# 00A-095.net
KiCad netlist of a schematic drawn in EAGLE
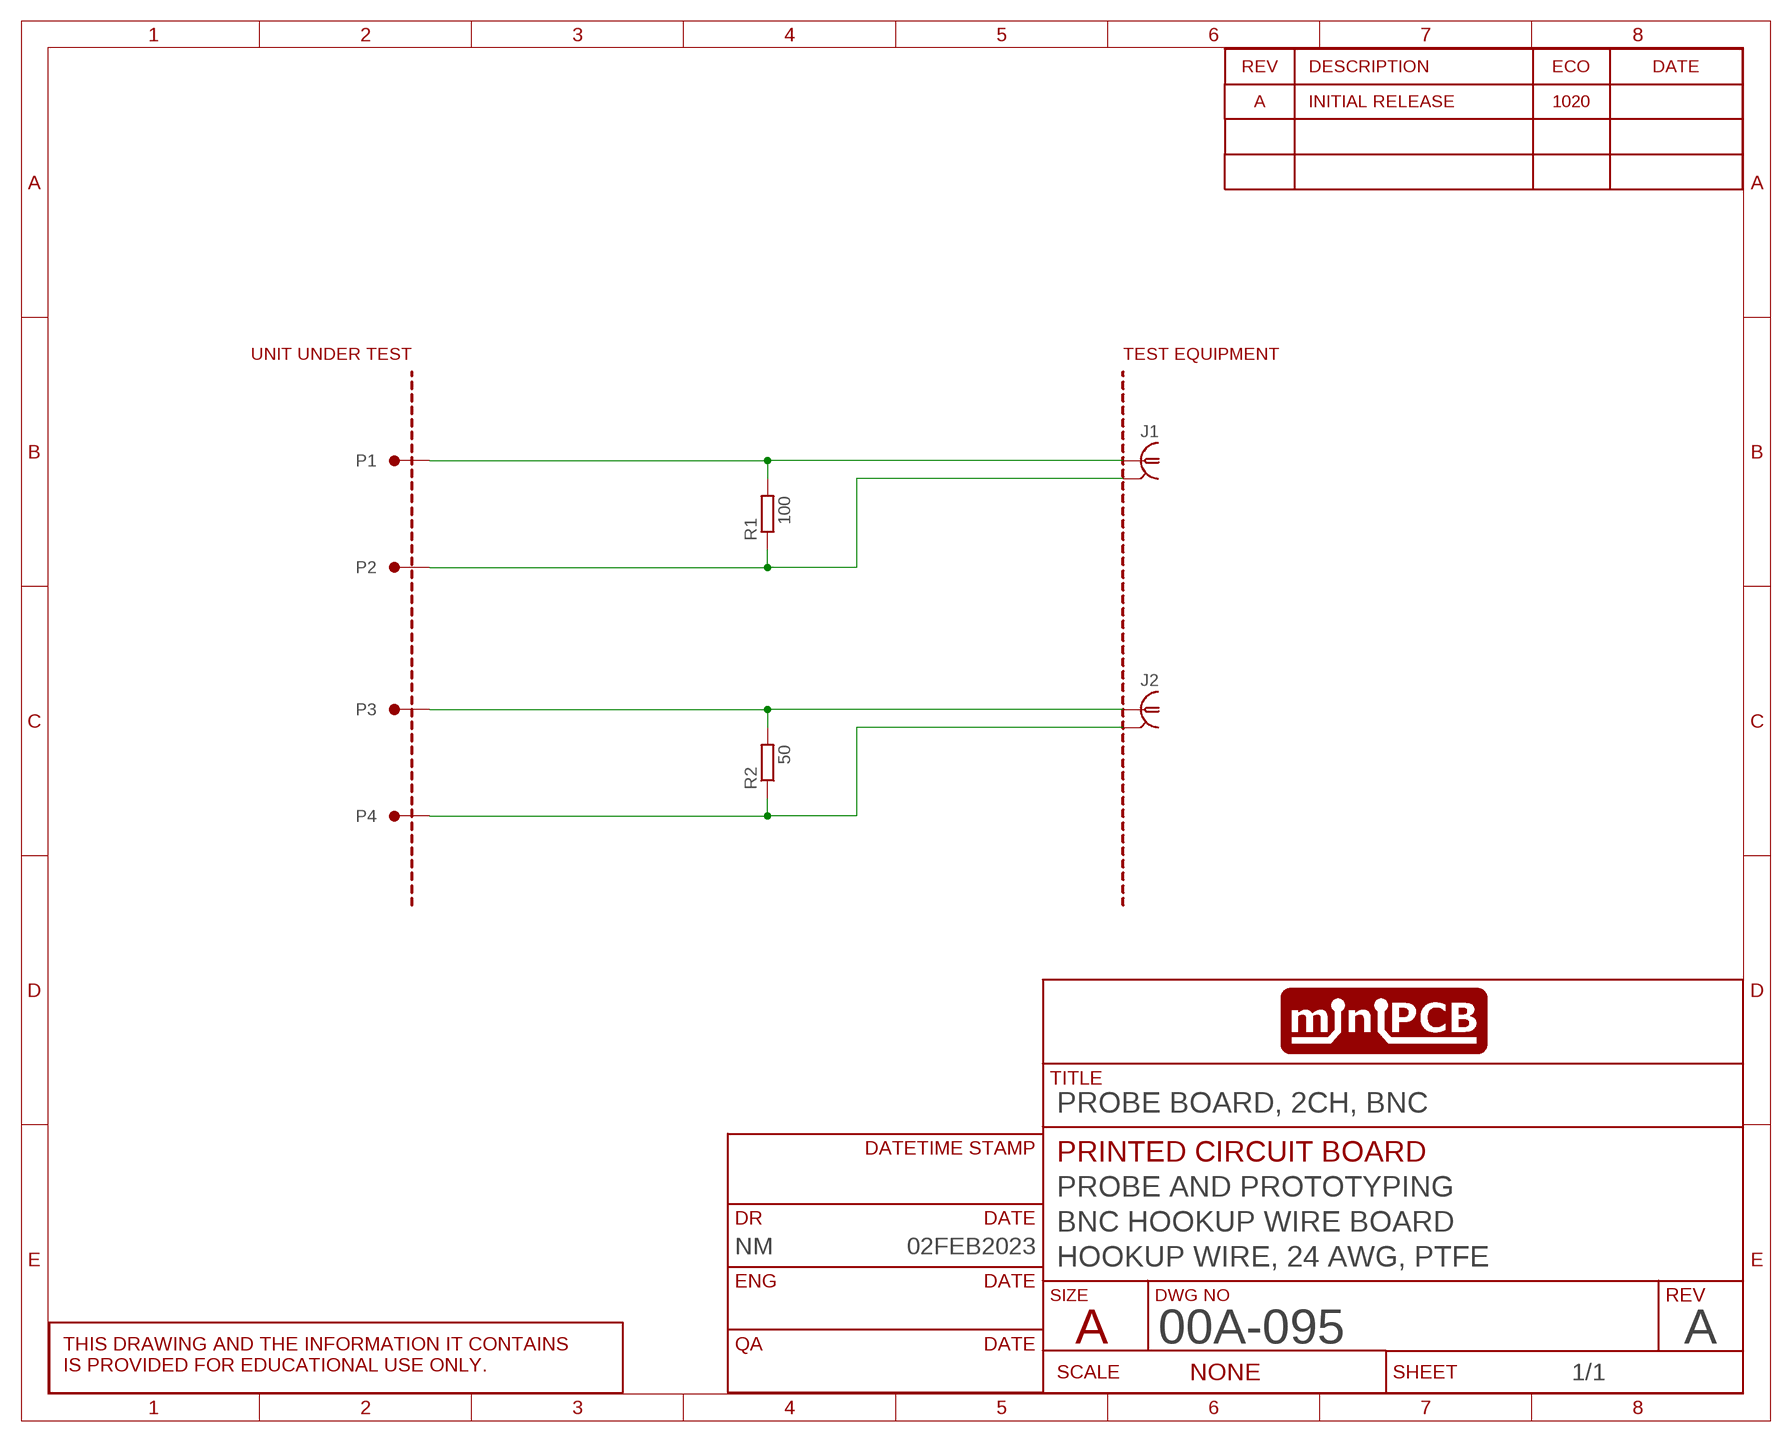
[diagram p0: schematic, sheet 1]

(export (version "E")
  (design (tool "Eeschema 10.0.6"))
  (components
    (comp (ref "J1")
      (value "BNC_RA")
      (footprint "eagle-import:BNC_RIGHTANGLE")
      (libsource (lib "eagle-import") (part "BNC_RA"))
    )
    (comp (ref "J2")
      (value "BNC_RA")
      (footprint "eagle-import:BNC_RIGHTANGLE")
      (libsource (lib "eagle-import") (part "BNC_RA"))
    )
    (comp (ref "P1")
      (value "PINS_124AWG-NOTEXT")
      (footprint "eagle-import:PINS_1_1MM-NOTEXT")
      (libsource (lib "eagle-import") (part "PINS_124AWG-NOTEXT"))
    )
    (comp (ref "P2")
      (value "PINS_124AWG-NOTEXT")
      (footprint "eagle-import:PINS_1_1MM-NOTEXT")
      (libsource (lib "eagle-import") (part "PINS_124AWG-NOTEXT"))
    )
    (comp (ref "P3")
      (value "PINS_124AWG-NOTEXT")
      (footprint "eagle-import:PINS_1_1MM-NOTEXT")
      (libsource (lib "eagle-import") (part "PINS_124AWG-NOTEXT"))
    )
    (comp (ref "P4")
      (value "PINS_124AWG-NOTEXT")
      (footprint "eagle-import:PINS_1_1MM-NOTEXT")
      (libsource (lib "eagle-import") (part "PINS_124AWG-NOTEXT"))
    )
    (comp (ref "PCB1")
      (value "MINIPCB_0P50X50")
      (footprint "eagle-import:MINIPCB_0P_50X50MM")
      (fields (field (name "PART_NUMBER") "00A-095-A"))
      (libsource (lib "eagle-import") (part "MINIPCB_0P50X50"))
    )
    (comp (ref "R1")
      (value "100")
      (footprint "eagle-import:R0805")
      (libsource (lib "eagle-import") (part "RESISTORSMD"))
    )
    (comp (ref "R2")
      (value "50")
      (footprint "eagle-import:R0805")
      (libsource (lib "eagle-import") (part "RESISTORSMD"))
    )
  )
  (nets
    (net (code "1") (name "Net-(J1-GND)") (class "Default")
      (node (ref "J1") (pin "2") (pinfunction "GND_2") (pintype "power_in"))
      (node (ref "P2") (pin "1") (pinfunction "1_1") (pintype "bidirectional"))
      (node (ref "P2") (pin "2") (pinfunction "1_2") (pintype "bidirectional"))
      (node (ref "R1") (pin "1") (pinfunction "1_1") (pintype "passive"))
    )
    (net (code "2") (name "Net-(J1-Pad1)") (class "Default")
      (node (ref "J1") (pin "1") (pinfunction "1_1") (pintype "passive"))
      (node (ref "P1") (pin "1") (pinfunction "1_1") (pintype "bidirectional"))
      (node (ref "P1") (pin "2") (pinfunction "1_2") (pintype "bidirectional"))
      (node (ref "R1") (pin "2") (pinfunction "2_2") (pintype "passive"))
    )
    (net (code "3") (name "Net-(J2-GND)") (class "Default")
      (node (ref "J2") (pin "2") (pinfunction "GND_2") (pintype "power_in"))
      (node (ref "P4") (pin "1") (pinfunction "1_1") (pintype "bidirectional"))
      (node (ref "P4") (pin "2") (pinfunction "1_2") (pintype "bidirectional"))
      (node (ref "R2") (pin "1") (pinfunction "1_1") (pintype "passive"))
    )
    (net (code "4") (name "Net-(J2-Pad1)") (class "Default")
      (node (ref "J2") (pin "1") (pinfunction "1_1") (pintype "passive"))
      (node (ref "P3") (pin "1") (pinfunction "1_1") (pintype "bidirectional"))
      (node (ref "P3") (pin "2") (pinfunction "1_2") (pintype "bidirectional"))
      (node (ref "R2") (pin "2") (pinfunction "2_2") (pintype "passive"))
    )
  )
)
